# Example_FPC_Stinffener_Design.net
KiCad netlist of a schematic drawn in EasyEDA Pro
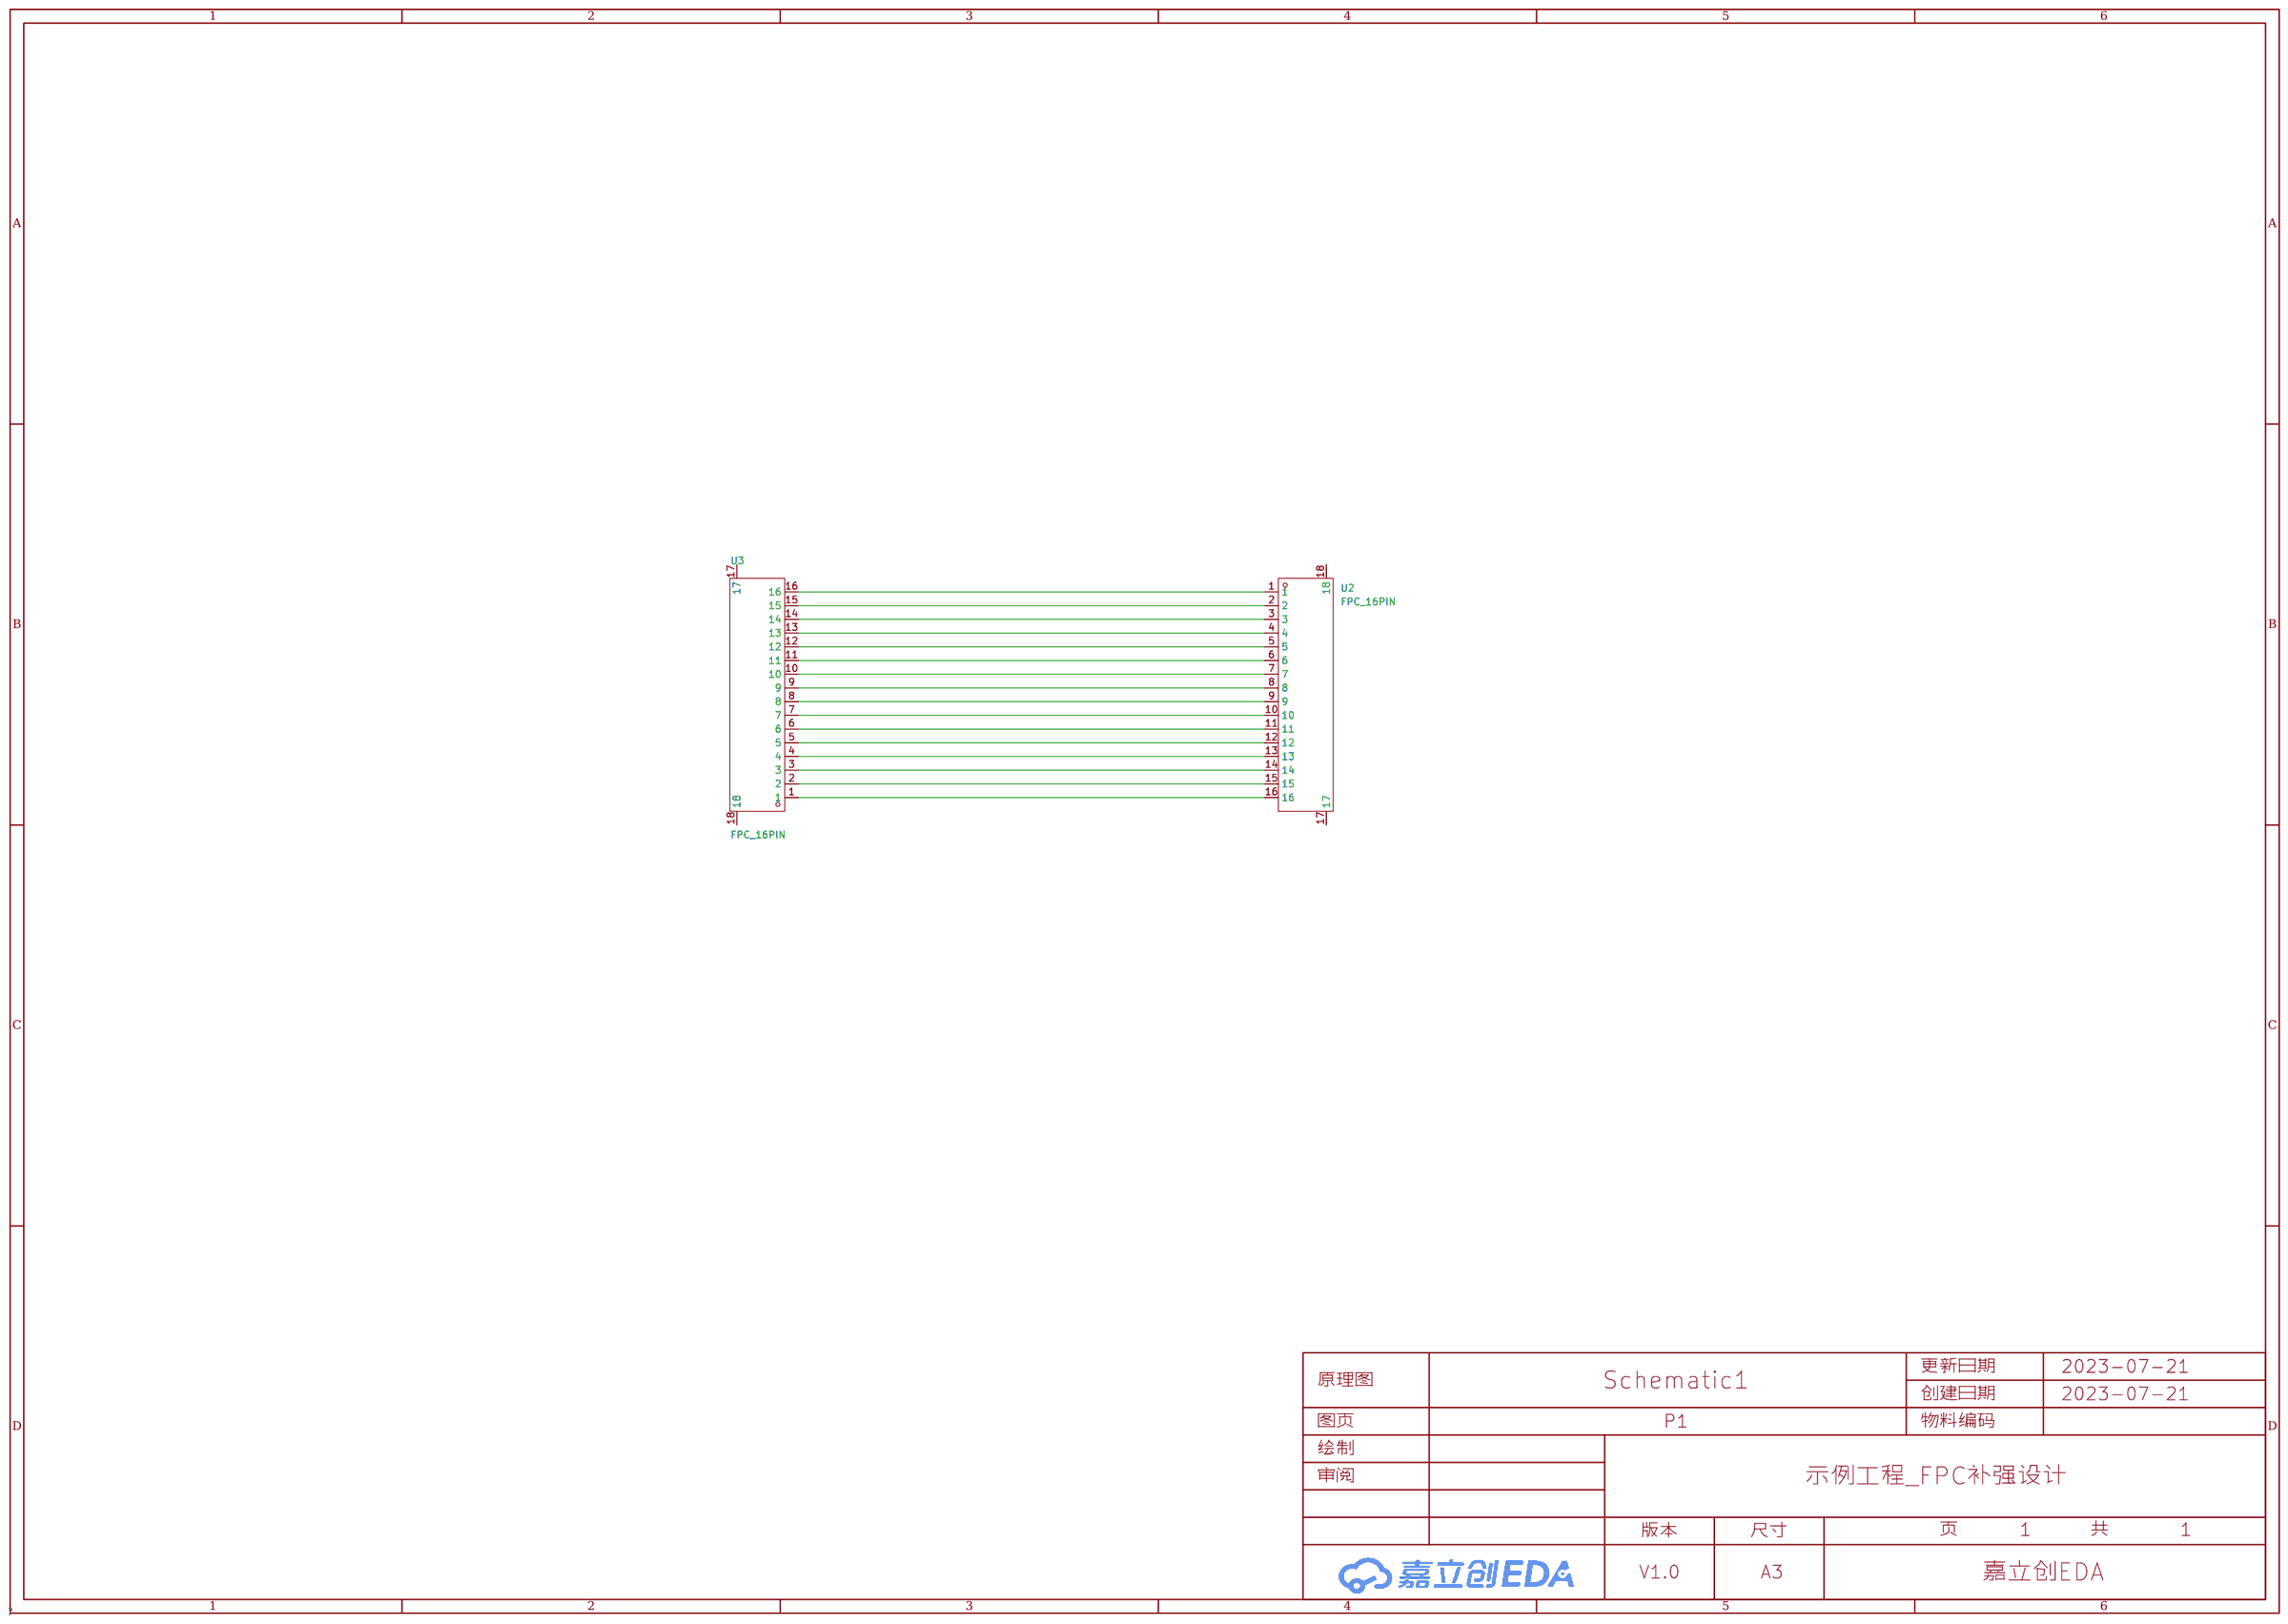
[diagram p0: schematic sheet]

(export (version "E")
  (design (tool "Eeschema 10.0.6"))
  (components
    (comp (ref "U2")
      (value "FPC_16PIN")
      (footprint "easyedapro:FPC-SMD_16P-P0.50_C9900010530")
      (libsource (lib "easyedapro") (part "FPC_16PIN"))
    )
    (comp (ref "U3")
      (value "FPC_16PIN")
      (footprint "easyedapro:FPC-SMD_16P-P0.50_C9900010530")
      (libsource (lib "easyedapro") (part "FPC_16PIN"))
    )
  )
  (nets
    (net (code "1") (name "Net-(U2-Pad1)") (class "Default")
      (node (ref "U2") (pin "1") (pinfunction "1_1") (pintype "input"))
      (node (ref "U3") (pin "16") (pinfunction "16_16") (pintype "input"))
    )
    (net (code "2") (name "Net-(U2-Pad2)") (class "Default")
      (node (ref "U2") (pin "2") (pinfunction "2_2") (pintype "input"))
      (node (ref "U3") (pin "15") (pinfunction "15_15") (pintype "input"))
    )
    (net (code "3") (name "Net-(U2-Pad3)") (class "Default")
      (node (ref "U2") (pin "3") (pinfunction "3_3") (pintype "input"))
      (node (ref "U3") (pin "14") (pinfunction "14_14") (pintype "input"))
    )
    (net (code "4") (name "Net-(U2-Pad4)") (class "Default")
      (node (ref "U2") (pin "4") (pinfunction "4_4") (pintype "input"))
      (node (ref "U3") (pin "13") (pinfunction "13_13") (pintype "input"))
    )
    (net (code "5") (name "Net-(U2-Pad5)") (class "Default")
      (node (ref "U2") (pin "5") (pinfunction "5_5") (pintype "input"))
      (node (ref "U3") (pin "12") (pinfunction "12_12") (pintype "input"))
    )
    (net (code "6") (name "Net-(U2-Pad6)") (class "Default")
      (node (ref "U2") (pin "6") (pinfunction "6_6") (pintype "input"))
      (node (ref "U3") (pin "11") (pinfunction "11_11") (pintype "input"))
    )
    (net (code "7") (name "Net-(U2-Pad7)") (class "Default")
      (node (ref "U2") (pin "7") (pinfunction "7_7") (pintype "input"))
      (node (ref "U3") (pin "10") (pinfunction "10_10") (pintype "input"))
    )
    (net (code "8") (name "Net-(U2-Pad8)") (class "Default")
      (node (ref "U2") (pin "8") (pinfunction "8_8") (pintype "input"))
      (node (ref "U3") (pin "9") (pinfunction "9_9") (pintype "input"))
    )
    (net (code "9") (name "Net-(U2-Pad9)") (class "Default")
      (node (ref "U2") (pin "9") (pinfunction "9_9") (pintype "input"))
      (node (ref "U3") (pin "8") (pinfunction "8_8") (pintype "input"))
    )
    (net (code "10") (name "Net-(U2-Pad10)") (class "Default")
      (node (ref "U2") (pin "10") (pinfunction "10_10") (pintype "input"))
      (node (ref "U3") (pin "7") (pinfunction "7_7") (pintype "input"))
    )
    (net (code "11") (name "Net-(U2-Pad11)") (class "Default")
      (node (ref "U2") (pin "11") (pinfunction "11_11") (pintype "input"))
      (node (ref "U3") (pin "6") (pinfunction "6_6") (pintype "input"))
    )
    (net (code "12") (name "Net-(U2-Pad12)") (class "Default")
      (node (ref "U2") (pin "12") (pinfunction "12_12") (pintype "input"))
      (node (ref "U3") (pin "5") (pinfunction "5_5") (pintype "input"))
    )
    (net (code "13") (name "Net-(U2-Pad13)") (class "Default")
      (node (ref "U2") (pin "13") (pinfunction "13_13") (pintype "input"))
      (node (ref "U3") (pin "4") (pinfunction "4_4") (pintype "input"))
    )
    (net (code "14") (name "Net-(U2-Pad14)") (class "Default")
      (node (ref "U2") (pin "14") (pinfunction "14_14") (pintype "input"))
      (node (ref "U3") (pin "3") (pinfunction "3_3") (pintype "input"))
    )
    (net (code "15") (name "Net-(U2-Pad15)") (class "Default")
      (node (ref "U2") (pin "15") (pinfunction "15_15") (pintype "input"))
      (node (ref "U3") (pin "2") (pinfunction "2_2") (pintype "input"))
    )
    (net (code "16") (name "Net-(U2-Pad16)") (class "Default")
      (node (ref "U2") (pin "16") (pinfunction "16_16") (pintype "input"))
      (node (ref "U3") (pin "1") (pinfunction "1_1") (pintype "input"))
    )
    (net (code "17") (name "unconnected-(U2-Pad17)") (class "Default")
      (node (ref "U2") (pin "17") (pinfunction "17_17") (pintype "input"))
    )
    (net (code "18") (name "unconnected-(U2-Pad18)") (class "Default")
      (node (ref "U2") (pin "18") (pinfunction "18_18") (pintype "input"))
    )
    (net (code "19") (name "unconnected-(U3-Pad17)") (class "Default")
      (node (ref "U3") (pin "17") (pinfunction "17_17") (pintype "input"))
    )
    (net (code "20") (name "unconnected-(U3-Pad18)") (class "Default")
      (node (ref "U3") (pin "18") (pinfunction "18_18") (pintype "input"))
    )
  )
)
